# 7_3_VA_PRORECT_LATCH_AND_CLEAR.net
KiCad netlist of a schematic drawn in Altium Designer
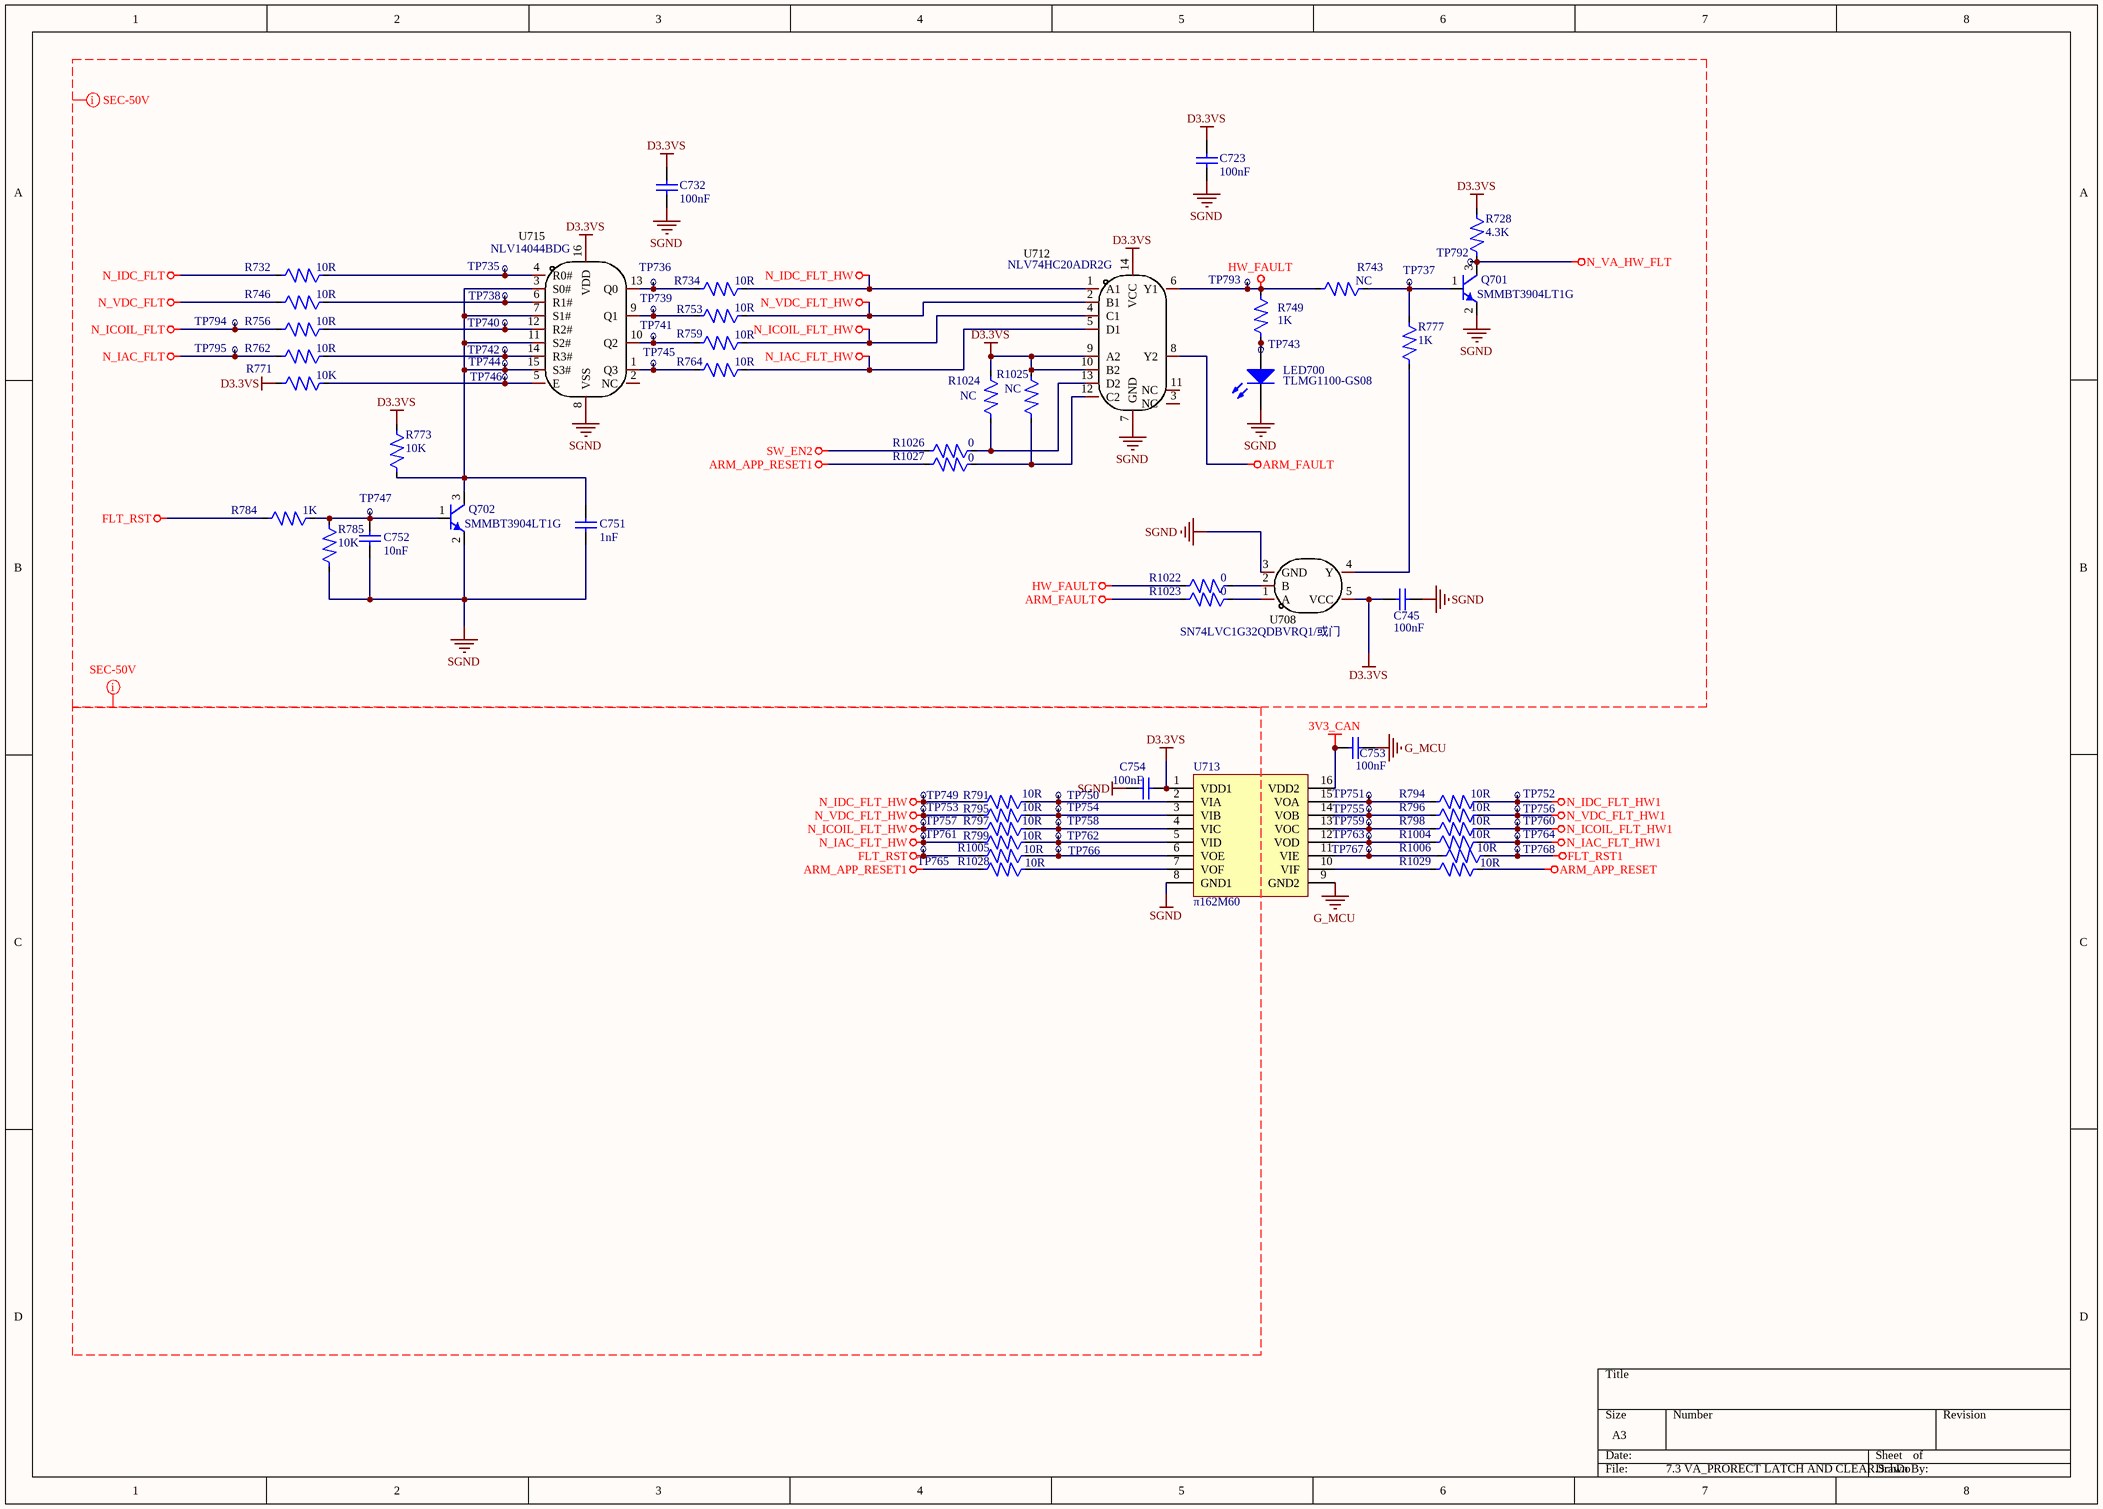
[diagram p0: 7.3 VA_PRORECT LATCH AND CLEAR.SchDoc]

(export (version "E")
  (design (tool "Eeschema 10.0.6"))
  (components
    (comp (ref "C723")
      (value "100nF")
      (footprint "C0402")
      (fields (field (name "MANUFACTURER") "Yageo"))
      (libsource (lib "*") (part "Cap"))
    )
    (comp (ref "C732")
      (value "100nF")
      (footprint "C0402")
      (fields (field (name "MANUFACTURER") "Yageo"))
      (libsource (lib "*") (part "Cap"))
    )
    (comp (ref "C745")
      (value "100nF")
      (footprint "C0402")
      (fields (field (name "MANUFACTURER") "Yageo"))
      (libsource (lib "*") (part "Cap"))
    )
    (comp (ref "C751")
      (value "1nF")
      (footprint "C0402")
      (description "CAP")
      (libsource (lib "HUNENG") (part "CAP"))
    )
    (comp (ref "C752")
      (value "10nF")
      (footprint "C0402")
      (description "CAP")
      (libsource (lib "HUNENG") (part "CAP"))
    )
    (comp (ref "C753")
      (value "100nF")
      (footprint "C0402")
      (fields (field (name "MANUFACTURER") "Yageo"))
      (libsource (lib "*") (part "Cap"))
    )
    (comp (ref "C754")
      (value "100nF")
      (footprint "C0402")
      (fields (field (name "MANUFACTURER") "Yageo"))
      (libsource (lib "*") (part "Cap"))
    )
    (comp (ref "LED700")
      (value "TLMG1100-GS08")
      (footprint "LED_0603")
      (libsource (lib "altium-import") (part "root_3_mirrored_LED1_"))
    )
    (comp (ref "Q701")
      (value "SMMBT3904LT1G")
      (footprint "SOT-23-3")
      (libsource (lib "原理图符号库2.0") (part "NPN"))
    )
    (comp (ref "Q702")
      (value "SMMBT3904LT1G")
      (footprint "SOT-23-3")
      (libsource (lib "原理图符号库2.0") (part "NPN"))
    )
    (comp (ref "R728")
      (value "4.3K")
      (footprint "R0402")
      (fields (field (name "MANUFACTURER") "Yageo"))
      (libsource (lib "GENERAL") (part "RESISTOR_0805"))
    )
    (comp (ref "R732")
      (value "10R")
      (footprint "R0402")
      (fields (field (name "MANUFACTURER") "Yageo"))
      (libsource (lib "GENERAL") (part "RESISTOR_0805"))
    )
    (comp (ref "R734")
      (value "10R")
      (footprint "R0402")
      (fields (field (name "MANUFACTURER") "Yageo"))
      (libsource (lib "GENERAL") (part "RESISTOR_0805"))
    )
    (comp (ref "R743")
      (value "NC")
      (footprint "R0402")
      (fields (field (name "MANUFACTURER") "Yageo"))
      (libsource (lib "GENERAL") (part "RESISTOR_0805"))
    )
    (comp (ref "R746")
      (value "10R")
      (footprint "R0402")
      (fields (field (name "MANUFACTURER") "Yageo"))
      (libsource (lib "GENERAL") (part "RESISTOR_0805"))
    )
    (comp (ref "R749")
      (value "1K")
      (footprint "R0402")
      (fields (field (name "MANUFACTURER") "Yageo"))
      (libsource (lib "GENERAL") (part "RESISTOR_0805"))
    )
    (comp (ref "R753")
      (value "10R")
      (footprint "R0402")
      (fields (field (name "MANUFACTURER") "Yageo"))
      (libsource (lib "GENERAL") (part "RESISTOR_0805"))
    )
    (comp (ref "R756")
      (value "10R")
      (footprint "R0402")
      (fields (field (name "MANUFACTURER") "Yageo"))
      (libsource (lib "GENERAL") (part "RESISTOR_0805"))
    )
    (comp (ref "R759")
      (value "10R")
      (footprint "R0402")
      (fields (field (name "MANUFACTURER") "Yageo"))
      (libsource (lib "GENERAL") (part "RESISTOR_0805"))
    )
    (comp (ref "R762")
      (value "10R")
      (footprint "R0402")
      (fields (field (name "MANUFACTURER") "Yageo"))
      (libsource (lib "GENERAL") (part "RESISTOR_0805"))
    )
    (comp (ref "R764")
      (value "10R")
      (footprint "R0402")
      (fields (field (name "MANUFACTURER") "Yageo"))
      (libsource (lib "GENERAL") (part "RESISTOR_0805"))
    )
    (comp (ref "R771")
      (value "10K")
      (footprint "R0402")
      (fields (field (name "MANUFACTURER") "Yageo"))
      (libsource (lib "GENERAL") (part "RESISTOR_0805"))
    )
    (comp (ref "R773")
      (value "10K")
      (footprint "R0402")
      (fields (field (name "MANUFACTURER") "Yageo"))
      (libsource (lib "GENERAL") (part "RESISTOR_0805"))
    )
    (comp (ref "R777")
      (value "1K")
      (footprint "R0402")
      (fields (field (name "MANUFACTURER") "Yageo"))
      (libsource (lib "GENERAL") (part "RESISTOR_0805"))
    )
    (comp (ref "R784")
      (value "1K")
      (footprint "R0402")
      (fields (field (name "MANUFACTURER") "Yageo"))
      (libsource (lib "GENERAL") (part "RESISTOR_0805"))
    )
    (comp (ref "R785")
      (value "10K")
      (footprint "R0402")
      (fields (field (name "MANUFACTURER") "Yageo"))
      (libsource (lib "GENERAL") (part "RESISTOR_0805"))
    )
    (comp (ref "R791")
      (value "10R")
      (footprint "R0402")
      (fields (field (name "MANUFACTURER") "Yageo"))
      (libsource (lib "GENERAL") (part "RESISTOR_0805"))
    )
    (comp (ref "R794")
      (value "10R")
      (footprint "R0402")
      (fields (field (name "MANUFACTURER") "Yageo"))
      (libsource (lib "GENERAL") (part "RESISTOR_0805"))
    )
    (comp (ref "R795")
      (value "10R")
      (footprint "R0402")
      (fields (field (name "MANUFACTURER") "Yageo"))
      (libsource (lib "GENERAL") (part "RESISTOR_0805"))
    )
    (comp (ref "R796")
      (value "10R")
      (footprint "R0402")
      (fields (field (name "MANUFACTURER") "Yageo"))
      (libsource (lib "GENERAL") (part "RESISTOR_0805"))
    )
    (comp (ref "R797")
      (value "10R")
      (footprint "R0402")
      (fields (field (name "MANUFACTURER") "Yageo"))
      (libsource (lib "GENERAL") (part "RESISTOR_0805"))
    )
    (comp (ref "R798")
      (value "10R")
      (footprint "R0402")
      (fields (field (name "MANUFACTURER") "Yageo"))
      (libsource (lib "GENERAL") (part "RESISTOR_0805"))
    )
    (comp (ref "R799")
      (value "10R")
      (footprint "R0402")
      (fields (field (name "MANUFACTURER") "Yageo"))
      (libsource (lib "GENERAL") (part "RESISTOR_0805"))
    )
    (comp (ref "R1004")
      (value "10R")
      (footprint "R0402")
      (fields (field (name "MANUFACTURER") "Yageo"))
      (libsource (lib "GENERAL") (part "RESISTOR_0805"))
    )
    (comp (ref "R1005")
      (value "10R")
      (footprint "R0402")
      (fields (field (name "MANUFACTURER") "Yageo"))
      (libsource (lib "GENERAL") (part "RESISTOR_0805"))
    )
    (comp (ref "R1006")
      (value "10R")
      (footprint "R0402")
      (fields (field (name "MANUFACTURER") "Yageo"))
      (libsource (lib "GENERAL") (part "RESISTOR_0805"))
    )
    (comp (ref "R1022")
      (value "0")
      (footprint "R0402")
      (fields (field (name "MANUFACTURER") "Yageo"))
      (libsource (lib "GENERAL") (part "RESISTOR_0805"))
    )
    (comp (ref "R1023")
      (value "0")
      (footprint "R0402")
      (fields (field (name "MANUFACTURER") "Yageo"))
      (libsource (lib "GENERAL") (part "RESISTOR_0805"))
    )
    (comp (ref "R1024")
      (value "NC")
      (footprint "R0402")
      (fields (field (name "MANUFACTURER") "Yageo"))
      (libsource (lib "GENERAL") (part "RESISTOR_0805"))
    )
    (comp (ref "R1025")
      (value "NC")
      (footprint "R0402")
      (fields (field (name "MANUFACTURER") "Yageo"))
      (libsource (lib "GENERAL") (part "RESISTOR_0805"))
    )
    (comp (ref "R1026")
      (value "0")
      (footprint "R0402")
      (fields (field (name "MANUFACTURER") "Yageo"))
      (libsource (lib "GENERAL") (part "RESISTOR_0805"))
    )
    (comp (ref "R1027")
      (value "0")
      (footprint "R0402")
      (fields (field (name "MANUFACTURER") "Yageo"))
      (libsource (lib "GENERAL") (part "RESISTOR_0805"))
    )
    (comp (ref "R1028")
      (value "10R")
      (footprint "R0402")
      (fields (field (name "MANUFACTURER") "Yageo"))
      (libsource (lib "GENERAL") (part "RESISTOR_0805"))
    )
    (comp (ref "R1029")
      (value "10R")
      (footprint "R0402")
      (fields (field (name "MANUFACTURER") "Yageo"))
      (libsource (lib "GENERAL") (part "RESISTOR_0805"))
    )
    (comp (ref "TP735") (value "测试点") (footprint "测试点") (libsource (lib "原理图符号库2.0") (part "测试点")))
    (comp (ref "TP736") (value "测试点") (footprint "测试点") (libsource (lib "原理图符号库2.0") (part "测试点")))
    (comp (ref "TP737") (value "测试点") (footprint "测试点") (libsource (lib "原理图符号库2.0") (part "测试点")))
    (comp (ref "TP738") (value "测试点") (footprint "测试点") (libsource (lib "原理图符号库2.0") (part "测试点")))
    (comp (ref "TP739") (value "测试点") (footprint "测试点") (libsource (lib "原理图符号库2.0") (part "测试点")))
    (comp (ref "TP740") (value "测试点") (footprint "测试点") (libsource (lib "原理图符号库2.0") (part "测试点")))
    (comp (ref "TP741") (value "测试点") (footprint "测试点") (libsource (lib "原理图符号库2.0") (part "测试点")))
    (comp (ref "TP742") (value "测试点") (footprint "测试点") (libsource (lib "原理图符号库2.0") (part "测试点")))
    (comp (ref "TP743") (value "测试点") (footprint "测试点") (libsource (lib "原理图符号库2.0") (part "测试点")))
    (comp (ref "TP744") (value "测试点") (footprint "测试点") (libsource (lib "原理图符号库2.0") (part "测试点")))
    (comp (ref "TP745") (value "测试点") (footprint "测试点") (libsource (lib "原理图符号库2.0") (part "测试点")))
    (comp (ref "TP746") (value "测试点") (footprint "测试点") (libsource (lib "原理图符号库2.0") (part "测试点")))
    (comp (ref "TP747") (value "测试点") (footprint "测试点") (libsource (lib "原理图符号库2.0") (part "测试点")))
    (comp (ref "TP749") (value "测试点") (footprint "测试点") (libsource (lib "原理图符号库2.0") (part "测试点")))
    (comp (ref "TP750") (value "测试点") (footprint "测试点") (libsource (lib "原理图符号库2.0") (part "测试点")))
    (comp (ref "TP751") (value "测试点") (footprint "测试点") (libsource (lib "原理图符号库2.0") (part "测试点")))
    (comp (ref "TP752") (value "测试点") (footprint "测试点") (libsource (lib "原理图符号库2.0") (part "测试点")))
    (comp (ref "TP753") (value "测试点") (footprint "测试点") (libsource (lib "原理图符号库2.0") (part "测试点")))
    (comp (ref "TP754") (value "测试点") (footprint "测试点") (libsource (lib "原理图符号库2.0") (part "测试点")))
    (comp (ref "TP755") (value "测试点") (footprint "测试点") (libsource (lib "原理图符号库2.0") (part "测试点")))
    (comp (ref "TP756") (value "测试点") (footprint "测试点") (libsource (lib "原理图符号库2.0") (part "测试点")))
    (comp (ref "TP757") (value "测试点") (footprint "测试点") (libsource (lib "原理图符号库2.0") (part "测试点")))
    (comp (ref "TP758") (value "测试点") (footprint "测试点") (libsource (lib "原理图符号库2.0") (part "测试点")))
    (comp (ref "TP759") (value "测试点") (footprint "测试点") (libsource (lib "原理图符号库2.0") (part "测试点")))
    (comp (ref "TP760") (value "测试点") (footprint "测试点") (libsource (lib "原理图符号库2.0") (part "测试点")))
    (comp (ref "TP761") (value "测试点") (footprint "测试点") (libsource (lib "原理图符号库2.0") (part "测试点")))
    (comp (ref "TP762") (value "测试点") (footprint "测试点") (libsource (lib "原理图符号库2.0") (part "测试点")))
    (comp (ref "TP763") (value "测试点") (footprint "测试点") (libsource (lib "原理图符号库2.0") (part "测试点")))
    (comp (ref "TP764") (value "测试点") (footprint "测试点") (libsource (lib "原理图符号库2.0") (part "测试点")))
    (comp (ref "TP765") (value "测试点") (footprint "测试点") (libsource (lib "原理图符号库2.0") (part "测试点")))
    (comp (ref "TP766") (value "测试点") (footprint "测试点") (libsource (lib "原理图符号库2.0") (part "测试点")))
    (comp (ref "TP767") (value "测试点") (footprint "测试点") (libsource (lib "原理图符号库2.0") (part "测试点")))
    (comp (ref "TP768") (value "测试点") (footprint "测试点") (libsource (lib "原理图符号库2.0") (part "测试点")))
    (comp (ref "TP792") (value "测试点") (footprint "测试点") (libsource (lib "原理图符号库2.0") (part "测试点")))
    (comp (ref "TP793") (value "测试点") (footprint "测试点") (libsource (lib "原理图符号库2.0") (part "测试点")))
    (comp (ref "TP794") (value "测试点") (footprint "测试点") (libsource (lib "原理图符号库2.0") (part "测试点")))
    (comp (ref "TP795") (value "测试点") (footprint "测试点") (libsource (lib "原理图符号库2.0") (part "测试点")))
    (comp (ref "U708")
      (value "SN74LVC1G32QDBVRQ1/或门")
      (footprint "SOT23-5")
      (fields
        (field (name "MANUFACTURER") "TI(德州仪器)")
        (field (name "MANUFACTURER PART") "SN74LVC1G08QDBVRQ1")
      )
      (libsource (lib "altium-import") (part "root_2_mirrored_SN74LVC1G08QDBVRQ1_"))
    )
    (comp (ref "U712")
      (value "NLV74HC20ADR2G")
      (footprint "PG_D_SO_14")
      (fields (field (name "MANUFACTURER") "onsemi(安森美)"))
      (libsource (lib "原理图符号库2.0") (part "NLV74HC20ADR2G"))
    )
    (comp (ref "U713")
      (value "π162M60")
      (footprint "SOIC_W_16")
      (libsource (lib "原理图符号库2.0") (part "162xxx"))
    )
    (comp (ref "U715")
      (value "NLV14044BDG")
      (footprint "SOIC_16_D")
      (fields (field (name "MANUFACTURER") "onsemi(安森美)"))
      (libsource (lib "原理图符号库2.0") (part "NLV14044BDG"))
    )
  )
  (nets
    (net (code "1") (name "3V3_CAN") (class "Default")
      (node (ref "C753") (pin "2") (pinfunction "2_2") (pintype "passive"))
      (node (ref "U713") (pin "16") (pinfunction "VDD2_16") (pintype "passive"))
    )
    (net (code "2") (name "ARM_APP_RESET") (class "Default")
      (node (ref "R1029") (pin "1") (pinfunction "1_1") (pintype "passive"))
    )
    (net (code "3") (name "ARM_APP_RESET1") (class "Default")
      (node (ref "R1027") (pin "2") (pinfunction "2_2") (pintype "passive"))
      (node (ref "R1028") (pin "2") (pinfunction "2_2") (pintype "passive"))
    )
    (net (code "4") (name "ARM_FAULT") (class "Default")
      (node (ref "R1023") (pin "2") (pinfunction "2_2") (pintype "passive"))
      (node (ref "U712") (pin "8") (pinfunction "Y2_8") (pintype "passive"))
    )
    (net (code "5") (name "D3.3VS") (class "Default")
      (node (ref "C723") (pin "1") (pinfunction "1_1") (pintype "passive"))
      (node (ref "C732") (pin "1") (pinfunction "1_1") (pintype "passive"))
      (node (ref "C745") (pin "1") (pinfunction "1_1") (pintype "passive"))
      (node (ref "C754") (pin "1") (pinfunction "1_1") (pintype "passive"))
      (node (ref "R1024") (pin "1") (pinfunction "1_1") (pintype "passive"))
      (node (ref "R1025") (pin "1") (pinfunction "1_1") (pintype "passive"))
      (node (ref "R728") (pin "1") (pinfunction "1_1") (pintype "passive"))
      (node (ref "R771") (pin "1") (pinfunction "1_1") (pintype "passive"))
      (node (ref "R773") (pin "1") (pinfunction "1_1") (pintype "passive"))
      (node (ref "U708") (pin "5") (pinfunction "VCC_5") (pintype "passive"))
      (node (ref "U712") (pin "10") (pinfunction "B2_10") (pintype "passive"))
      (node (ref "U712") (pin "14") (pinfunction "VCC_14") (pintype "passive"))
      (node (ref "U712") (pin "9") (pinfunction "A2_9") (pintype "passive"))
      (node (ref "U713") (pin "1") (pinfunction "VDD1_1") (pintype "passive"))
      (node (ref "U715") (pin "16") (pinfunction "VDD_16") (pintype "passive"))
    )
    (net (code "6") (name "FLT_RST") (class "Default")
      (node (ref "R1005") (pin "2") (pinfunction "2_2") (pintype "passive"))
      (node (ref "R784") (pin "2") (pinfunction "2_2") (pintype "passive"))
      (node (ref "TP765") (pin "1") (pinfunction "1_1") (pintype "passive"))
    )
    (net (code "7") (name "FLT_RST1") (class "Default")
      (node (ref "R1006") (pin "1") (pinfunction "1_1") (pintype "passive"))
      (node (ref "TP768") (pin "1") (pinfunction "1_1") (pintype "passive"))
    )
    (net (code "8") (name "G_MCU") (class "Default")
      (node (ref "C753") (pin "1") (pinfunction "1_1") (pintype "passive"))
      (node (ref "U713") (pin "9") (pinfunction "GND2_9") (pintype "passive"))
    )
    (net (code "9") (name "HW_FAULT") (class "Default")
      (node (ref "R1022") (pin "2") (pinfunction "2_2") (pintype "passive"))
      (node (ref "R743") (pin "2") (pinfunction "2_2") (pintype "passive"))
      (node (ref "R749") (pin "1") (pinfunction "1_1") (pintype "passive"))
      (node (ref "TP793") (pin "1") (pinfunction "1_1") (pintype "passive"))
      (node (ref "U712") (pin "6") (pinfunction "Y1_6") (pintype "passive"))
    )
    (net (code "10") (name "N_IAC_FLT") (class "Default")
      (node (ref "R762") (pin "2") (pinfunction "2_2") (pintype "passive"))
      (node (ref "TP795") (pin "1") (pinfunction "1_1") (pintype "passive"))
    )
    (net (code "11") (name "N_IAC_FLT_HW") (class "Default")
      (node (ref "R764") (pin "1") (pinfunction "1_1") (pintype "passive"))
      (node (ref "R799") (pin "2") (pinfunction "2_2") (pintype "passive"))
      (node (ref "TP761") (pin "1") (pinfunction "1_1") (pintype "passive"))
      (node (ref "U712") (pin "5") (pinfunction "D1_5") (pintype "passive"))
    )
    (net (code "12") (name "N_IAC_FLT_HW1") (class "Default")
      (node (ref "R1004") (pin "1") (pinfunction "1_1") (pintype "passive"))
      (node (ref "TP764") (pin "1") (pinfunction "1_1") (pintype "passive"))
    )
    (net (code "13") (name "N_ICOIL_FLT") (class "Default")
      (node (ref "R756") (pin "2") (pinfunction "2_2") (pintype "passive"))
      (node (ref "TP794") (pin "1") (pinfunction "1_1") (pintype "passive"))
    )
    (net (code "14") (name "N_ICOIL_FLT_HW") (class "Default")
      (node (ref "R759") (pin "1") (pinfunction "1_1") (pintype "passive"))
      (node (ref "R797") (pin "2") (pinfunction "2_2") (pintype "passive"))
      (node (ref "TP757") (pin "1") (pinfunction "1_1") (pintype "passive"))
      (node (ref "U712") (pin "4") (pinfunction "C1_4") (pintype "passive"))
    )
    (net (code "15") (name "N_ICOIL_FLT_HW1") (class "Default")
      (node (ref "R798") (pin "1") (pinfunction "1_1") (pintype "passive"))
      (node (ref "TP760") (pin "1") (pinfunction "1_1") (pintype "passive"))
    )
    (net (code "16") (name "N_IDC_FLT") (class "Default")
      (node (ref "R732") (pin "2") (pinfunction "2_2") (pintype "passive"))
    )
    (net (code "17") (name "N_IDC_FLT_HW") (class "Default")
      (node (ref "R734") (pin "1") (pinfunction "1_1") (pintype "passive"))
      (node (ref "R791") (pin "2") (pinfunction "2_2") (pintype "passive"))
      (node (ref "TP749") (pin "1") (pinfunction "1_1") (pintype "passive"))
      (node (ref "U712") (pin "1") (pinfunction "A1_1") (pintype "passive"))
    )
    (net (code "18") (name "N_IDC_FLT_HW1") (class "Default")
      (node (ref "R794") (pin "1") (pinfunction "1_1") (pintype "passive"))
      (node (ref "TP752") (pin "1") (pinfunction "1_1") (pintype "passive"))
    )
    (net (code "19") (name "N_VA_HW_FLT") (class "Default")
      (node (ref "Q701") (pin "3") (pinfunction "C_3") (pintype "passive"))
      (node (ref "R728") (pin "2") (pinfunction "2_2") (pintype "passive"))
      (node (ref "TP792") (pin "1") (pinfunction "1_1") (pintype "passive"))
    )
    (net (code "20") (name "N_VDC_FLT") (class "Default")
      (node (ref "R746") (pin "2") (pinfunction "2_2") (pintype "passive"))
    )
    (net (code "21") (name "N_VDC_FLT_HW") (class "Default")
      (node (ref "R753") (pin "1") (pinfunction "1_1") (pintype "passive"))
      (node (ref "R795") (pin "2") (pinfunction "2_2") (pintype "passive"))
      (node (ref "TP753") (pin "1") (pinfunction "1_1") (pintype "passive"))
      (node (ref "U712") (pin "2") (pinfunction "B1_2") (pintype "passive"))
    )
    (net (code "22") (name "N_VDC_FLT_HW1") (class "Default")
      (node (ref "R796") (pin "1") (pinfunction "1_1") (pintype "passive"))
      (node (ref "TP756") (pin "1") (pinfunction "1_1") (pintype "passive"))
    )
    (net (code "23") (name "Net-(LED700-A)") (class "Default")
      (node (ref "LED700") (pin "1") (pinfunction "A_1") (pintype "passive"))
      (node (ref "R749") (pin "2") (pinfunction "2_2") (pintype "passive"))
      (node (ref "TP743") (pin "1") (pinfunction "1_1") (pintype "passive"))
    )
    (net (code "24") (name "Net-(Q701-B)") (class "Default")
      (node (ref "Q701") (pin "1") (pinfunction "B_1") (pintype "passive"))
      (node (ref "R743") (pin "1") (pinfunction "1_1") (pintype "passive"))
      (node (ref "R777") (pin "1") (pinfunction "1_1") (pintype "passive"))
      (node (ref "TP737") (pin "1") (pinfunction "1_1") (pintype "passive"))
    )
    (net (code "25") (name "Net-(Q702-B)") (class "Default")
      (node (ref "C752") (pin "2") (pinfunction "2_2") (pintype "passive"))
      (node (ref "Q702") (pin "1") (pinfunction "B_1") (pintype "passive"))
      (node (ref "R784") (pin "1") (pinfunction "1_1") (pintype "passive"))
      (node (ref "R785") (pin "1") (pinfunction "1_1") (pintype "passive"))
      (node (ref "TP747") (pin "1") (pinfunction "1_1") (pintype "passive"))
    )
    (net (code "26") (name "Net-(Q702-C)") (class "Default")
      (node (ref "C751") (pin "2") (pinfunction "2_2") (pintype "passive"))
      (node (ref "Q702") (pin "3") (pinfunction "C_3") (pintype "passive"))
      (node (ref "R773") (pin "2") (pinfunction "2_2") (pintype "passive"))
      (node (ref "TP744") (pin "1") (pinfunction "1_1") (pintype "passive"))
      (node (ref "U715") (pin "11") (pinfunction "S2#_11") (pintype "passive"))
      (node (ref "U715") (pin "15") (pinfunction "S3#_15") (pintype "passive"))
      (node (ref "U715") (pin "3") (pinfunction "S0#_3") (pintype "passive"))
      (node (ref "U715") (pin "7") (pinfunction "S1#_7") (pintype "passive"))
    )
    (net (code "27") (name "Net-(U708-A)") (class "Default")
      (node (ref "R1023") (pin "1") (pinfunction "1_1") (pintype "passive"))
      (node (ref "U708") (pin "1") (pinfunction "A_1") (pintype "passive"))
    )
    (net (code "28") (name "Net-(U708-B)") (class "Default")
      (node (ref "R1022") (pin "1") (pinfunction "1_1") (pintype "passive"))
      (node (ref "U708") (pin "2") (pinfunction "B_2") (pintype "passive"))
    )
    (net (code "29") (name "Net-(U708-Y)") (class "Default")
      (node (ref "R777") (pin "2") (pinfunction "2_2") (pintype "passive"))
      (node (ref "U708") (pin "4") (pinfunction "Y_4") (pintype "passive"))
    )
    (net (code "30") (name "Net-(U712-C2)") (class "Default")
      (node (ref "R1025") (pin "2") (pinfunction "2_2") (pintype "passive"))
      (node (ref "R1027") (pin "1") (pinfunction "1_1") (pintype "passive"))
      (node (ref "U712") (pin "12") (pinfunction "C2_12") (pintype "passive"))
    )
    (net (code "31") (name "Net-(U712-D2)") (class "Default")
      (node (ref "R1024") (pin "2") (pinfunction "2_2") (pintype "passive"))
      (node (ref "R1026") (pin "1") (pinfunction "1_1") (pintype "passive"))
      (node (ref "U712") (pin "13") (pinfunction "D2_13") (pintype "passive"))
    )
    (net (code "32") (name "Net-(U713-VIA)") (class "Default")
      (node (ref "R791") (pin "1") (pinfunction "1_1") (pintype "passive"))
      (node (ref "TP750") (pin "1") (pinfunction "1_1") (pintype "passive"))
      (node (ref "U713") (pin "2") (pinfunction "VIA_2") (pintype "passive"))
    )
    (net (code "33") (name "Net-(U713-VIB)") (class "Default")
      (node (ref "R795") (pin "1") (pinfunction "1_1") (pintype "passive"))
      (node (ref "TP754") (pin "1") (pinfunction "1_1") (pintype "passive"))
      (node (ref "U713") (pin "3") (pinfunction "VIB_3") (pintype "passive"))
    )
    (net (code "34") (name "Net-(U713-VIC)") (class "Default")
      (node (ref "R797") (pin "1") (pinfunction "1_1") (pintype "passive"))
      (node (ref "TP758") (pin "1") (pinfunction "1_1") (pintype "passive"))
      (node (ref "U713") (pin "4") (pinfunction "VIC_4") (pintype "passive"))
    )
    (net (code "35") (name "Net-(U713-VID)") (class "Default")
      (node (ref "R799") (pin "1") (pinfunction "1_1") (pintype "passive"))
      (node (ref "TP762") (pin "1") (pinfunction "1_1") (pintype "passive"))
      (node (ref "U713") (pin "5") (pinfunction "VID_5") (pintype "passive"))
    )
    (net (code "36") (name "Net-(U713-VIE)") (class "Default")
      (node (ref "R1006") (pin "2") (pinfunction "2_2") (pintype "passive"))
      (node (ref "TP767") (pin "1") (pinfunction "1_1") (pintype "passive"))
      (node (ref "U713") (pin "11") (pinfunction "VIE_11") (pintype "passive"))
    )
    (net (code "37") (name "Net-(U713-VIF)") (class "Default")
      (node (ref "R1029") (pin "2") (pinfunction "2_2") (pintype "passive"))
      (node (ref "U713") (pin "10") (pinfunction "VIF_10") (pintype "passive"))
    )
    (net (code "38") (name "Net-(U713-VOA)") (class "Default")
      (node (ref "R794") (pin "2") (pinfunction "2_2") (pintype "passive"))
      (node (ref "TP751") (pin "1") (pinfunction "1_1") (pintype "passive"))
      (node (ref "U713") (pin "15") (pinfunction "VOA_15") (pintype "passive"))
    )
    (net (code "39") (name "Net-(U713-VOB)") (class "Default")
      (node (ref "R796") (pin "2") (pinfunction "2_2") (pintype "passive"))
      (node (ref "TP755") (pin "1") (pinfunction "1_1") (pintype "passive"))
      (node (ref "U713") (pin "14") (pinfunction "VOB_14") (pintype "passive"))
    )
    (net (code "40") (name "Net-(U713-VOC)") (class "Default")
      (node (ref "R798") (pin "2") (pinfunction "2_2") (pintype "passive"))
      (node (ref "TP759") (pin "1") (pinfunction "1_1") (pintype "passive"))
      (node (ref "U713") (pin "13") (pinfunction "VOC_13") (pintype "passive"))
    )
    (net (code "41") (name "Net-(U713-VOD)") (class "Default")
      (node (ref "R1004") (pin "2") (pinfunction "2_2") (pintype "passive"))
      (node (ref "TP763") (pin "1") (pinfunction "1_1") (pintype "passive"))
      (node (ref "U713") (pin "12") (pinfunction "VOD_12") (pintype "passive"))
    )
    (net (code "42") (name "Net-(U713-VOE)") (class "Default")
      (node (ref "R1005") (pin "1") (pinfunction "1_1") (pintype "passive"))
      (node (ref "TP766") (pin "1") (pinfunction "1_1") (pintype "passive"))
      (node (ref "U713") (pin "6") (pinfunction "VOE_6") (pintype "passive"))
    )
    (net (code "43") (name "Net-(U713-VOF)") (class "Default")
      (node (ref "R1028") (pin "1") (pinfunction "1_1") (pintype "passive"))
      (node (ref "U713") (pin "7") (pinfunction "VOF_7") (pintype "passive"))
    )
    (net (code "44") (name "Net-(U715-E)") (class "Default")
      (node (ref "R771") (pin "2") (pinfunction "2_2") (pintype "passive"))
      (node (ref "TP746") (pin "1") (pinfunction "1_1") (pintype "passive"))
      (node (ref "U715") (pin "5") (pinfunction "E_5") (pintype "passive"))
    )
    (net (code "45") (name "Net-(U715-Q0)") (class "Default")
      (node (ref "R734") (pin "2") (pinfunction "2_2") (pintype "passive"))
      (node (ref "TP736") (pin "1") (pinfunction "1_1") (pintype "passive"))
      (node (ref "U715") (pin "13") (pinfunction "Q0_13") (pintype "passive"))
    )
    (net (code "46") (name "Net-(U715-Q1)") (class "Default")
      (node (ref "R753") (pin "2") (pinfunction "2_2") (pintype "passive"))
      (node (ref "TP739") (pin "1") (pinfunction "1_1") (pintype "passive"))
      (node (ref "U715") (pin "9") (pinfunction "Q1_9") (pintype "passive"))
    )
    (net (code "47") (name "Net-(U715-Q2)") (class "Default")
      (node (ref "R759") (pin "2") (pinfunction "2_2") (pintype "passive"))
      (node (ref "TP741") (pin "1") (pinfunction "1_1") (pintype "passive"))
      (node (ref "U715") (pin "10") (pinfunction "Q2_10") (pintype "passive"))
    )
    (net (code "48") (name "Net-(U715-Q3)") (class "Default")
      (node (ref "R764") (pin "2") (pinfunction "2_2") (pintype "passive"))
      (node (ref "TP745") (pin "1") (pinfunction "1_1") (pintype "passive"))
      (node (ref "U715") (pin "1") (pinfunction "Q3_1") (pintype "passive"))
    )
    (net (code "49") (name "Net-(U715-R0#)") (class "Default")
      (node (ref "R732") (pin "1") (pinfunction "1_1") (pintype "passive"))
      (node (ref "TP735") (pin "1") (pinfunction "1_1") (pintype "passive"))
      (node (ref "U715") (pin "4") (pinfunction "R0#_4") (pintype "passive"))
    )
    (net (code "50") (name "Net-(U715-R1#)") (class "Default")
      (node (ref "R746") (pin "1") (pinfunction "1_1") (pintype "passive"))
      (node (ref "TP738") (pin "1") (pinfunction "1_1") (pintype "passive"))
      (node (ref "U715") (pin "6") (pinfunction "R1#_6") (pintype "passive"))
    )
    (net (code "51") (name "Net-(U715-R2#)") (class "Default")
      (node (ref "R756") (pin "1") (pinfunction "1_1") (pintype "passive"))
      (node (ref "TP740") (pin "1") (pinfunction "1_1") (pintype "passive"))
      (node (ref "U715") (pin "12") (pinfunction "R2#_12") (pintype "passive"))
    )
    (net (code "52") (name "Net-(U715-R3#)") (class "Default")
      (node (ref "R762") (pin "1") (pinfunction "1_1") (pintype "passive"))
      (node (ref "TP742") (pin "1") (pinfunction "1_1") (pintype "passive"))
      (node (ref "U715") (pin "14") (pinfunction "R3#_14") (pintype "passive"))
    )
    (net (code "53") (name "SGND") (class "Default")
      (node (ref "C723") (pin "2") (pinfunction "2_2") (pintype "passive"))
      (node (ref "C732") (pin "2") (pinfunction "2_2") (pintype "passive"))
      (node (ref "C745") (pin "2") (pinfunction "2_2") (pintype "passive"))
      (node (ref "C751") (pin "1") (pinfunction "1_1") (pintype "passive"))
      (node (ref "C752") (pin "1") (pinfunction "1_1") (pintype "passive"))
      (node (ref "C754") (pin "2") (pinfunction "2_2") (pintype "passive"))
      (node (ref "LED700") (pin "2") (pinfunction "K_2") (pintype "passive"))
      (node (ref "Q701") (pin "2") (pinfunction "E_2") (pintype "passive"))
      (node (ref "Q702") (pin "2") (pinfunction "E_2") (pintype "passive"))
      (node (ref "R785") (pin "2") (pinfunction "2_2") (pintype "passive"))
      (node (ref "U708") (pin "3") (pinfunction "GND_3") (pintype "passive"))
      (node (ref "U712") (pin "7") (pinfunction "GND_7") (pintype "passive"))
      (node (ref "U713") (pin "8") (pinfunction "GND1_8") (pintype "passive"))
      (node (ref "U715") (pin "8") (pinfunction "VSS_8") (pintype "passive"))
    )
    (net (code "54") (name "SW_EN2") (class "Default")
      (node (ref "R1026") (pin "2") (pinfunction "2_2") (pintype "passive"))
    )
    (net (code "55") (name "unconnected-(U712-NC-Pad3)") (class "Default")
      (node (ref "U712") (pin "3") (pinfunction "NC_3") (pintype "passive"))
    )
    (net (code "56") (name "unconnected-(U712-NC-Pad11)") (class "Default")
      (node (ref "U712") (pin "11") (pinfunction "NC_11") (pintype "passive"))
    )
    (net (code "57") (name "unconnected-(U715-NC-Pad2)") (class "Default")
      (node (ref "U715") (pin "2") (pinfunction "NC_2") (pintype "passive"))
    )
  )
)
